# hexg-001.net
KiCad netlist of a schematic drawn in EAGLE
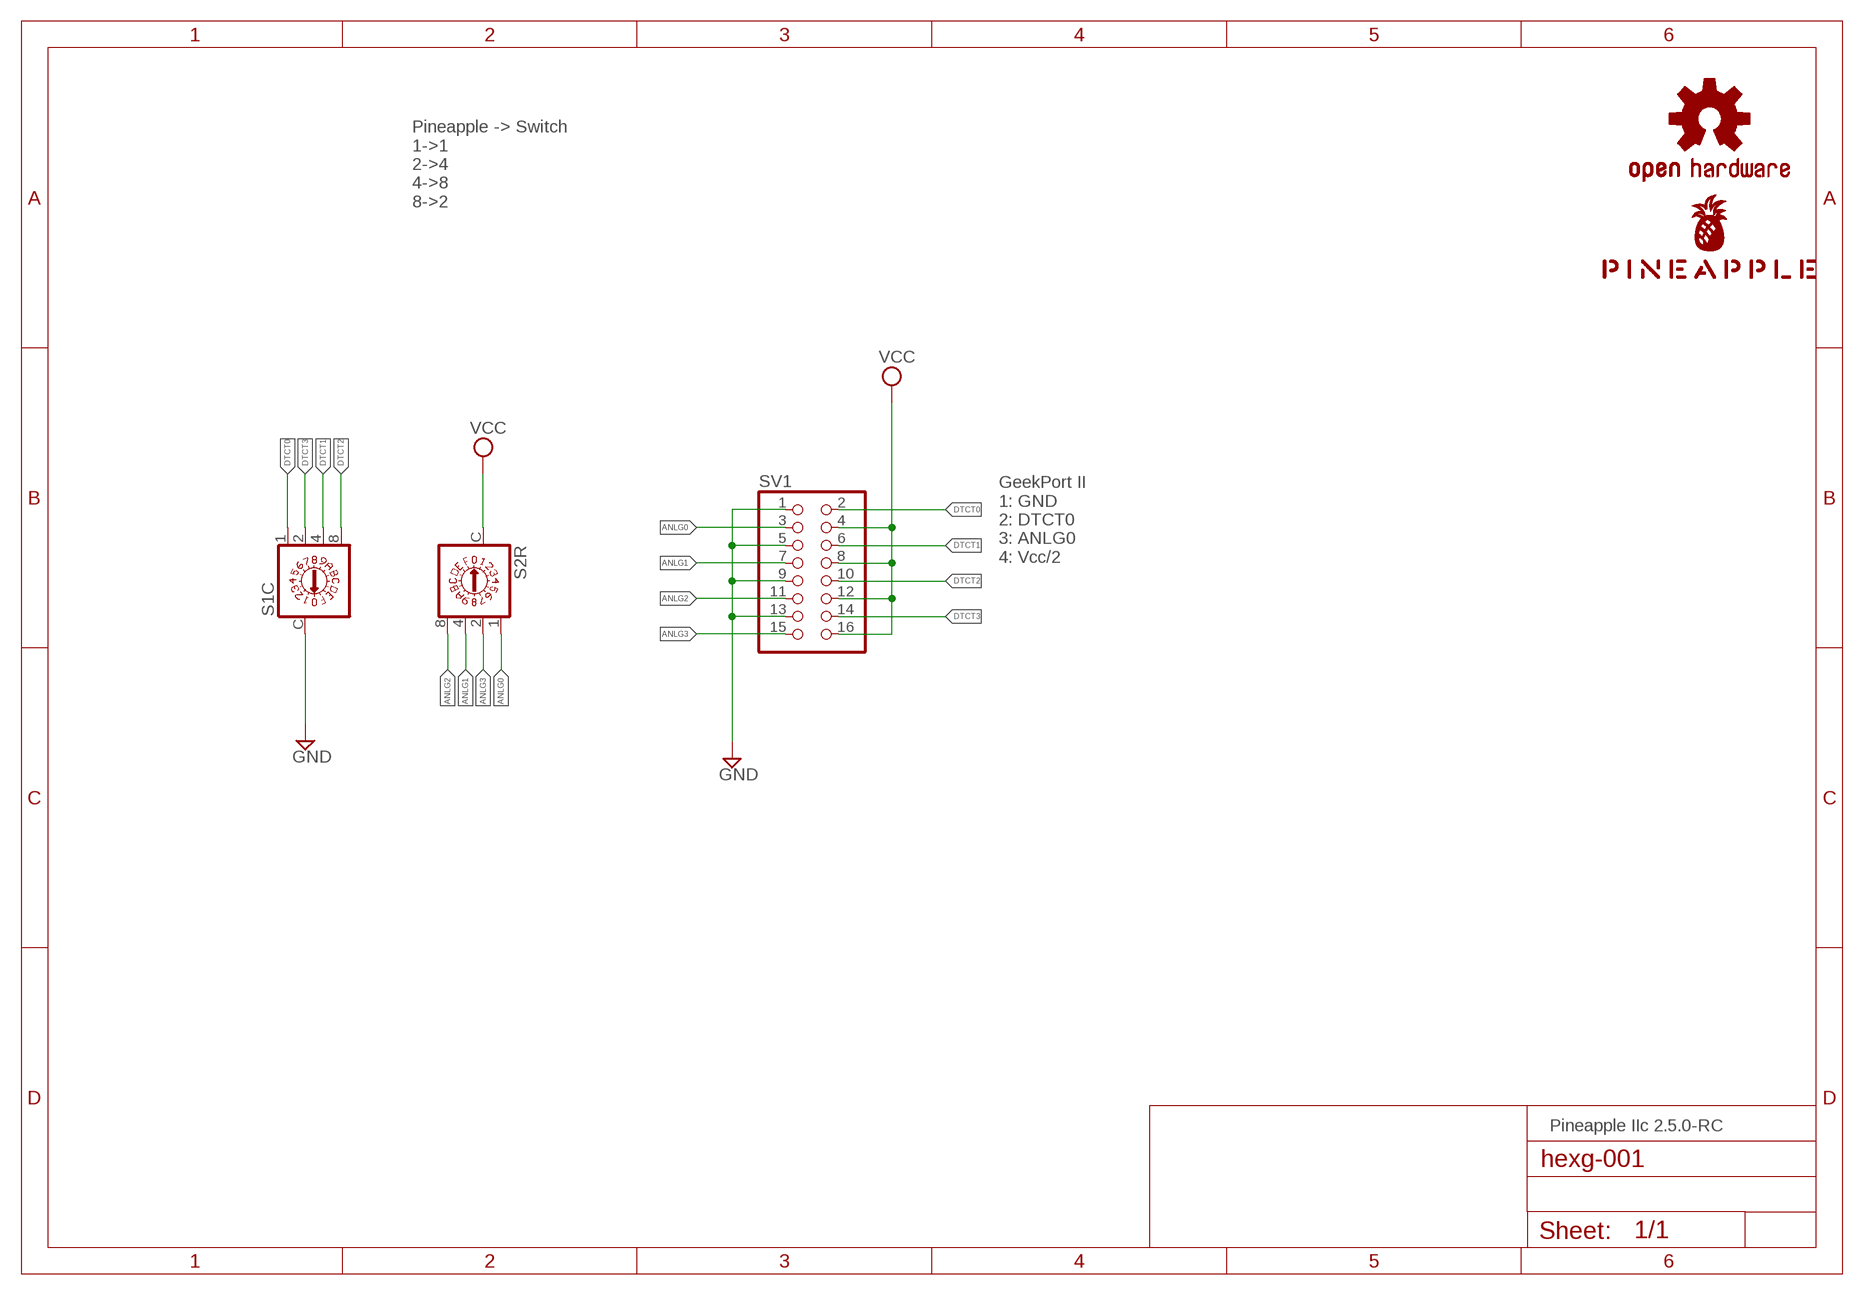
[diagram p0: schematic, sheet 1]

(export (version "E")
  (design (tool "Eeschema 10.0.6"))
  (components
    (comp (ref "LOGO1")
      (value "OSHW-LOGOS-COPPER")
      (footprint "eagle-import:OSHW-LOGO-S_COPPER")
      (libsource (lib "eagle-import") (part "OSHW-LOGOS-COPPER"))
    )
    (comp (ref "S1C")
      (value "A1353HEX")
      (footprint "eagle-import:A1353HEX")
      (libsource (lib "eagle-import") (part "A1353HEX"))
    )
    (comp (ref "S2R")
      (value "A1353HEX")
      (footprint "eagle-import:A1353HEX")
      (libsource (lib "eagle-import") (part "A1353HEX"))
    )
    (comp (ref "SV1")
      (value "PINHD-2X8")
      (footprint "eagle-import:2X08")
      (libsource (lib "eagle-import") (part "PINHD-2X8"))
    )
    (comp (ref "U$1")
      (value "PINEAPPLE450_SILK")
      (footprint "eagle-import:PINEAPPLE450_SILK")
      (libsource (lib "eagle-import") (part "PINEAPPLE450_SILK"))
    )
  )
  (nets
    (net (code "1") (name "ANLG0") (class "Default")
      (node (ref "S2R") (pin "1") (pinfunction "1_1") (pintype "passive"))
      (node (ref "SV1") (pin "3") (pinfunction "3_3") (pintype "passive"))
    )
    (net (code "2") (name "ANLG1") (class "Default")
      (node (ref "S2R") (pin "4") (pinfunction "4_4") (pintype "passive"))
      (node (ref "SV1") (pin "7") (pinfunction "7_7") (pintype "passive"))
    )
    (net (code "3") (name "ANLG2") (class "Default")
      (node (ref "S2R") (pin "8") (pinfunction "8_8") (pintype "passive"))
      (node (ref "SV1") (pin "11") (pinfunction "11_11") (pintype "passive"))
    )
    (net (code "4") (name "ANLG3") (class "Default")
      (node (ref "S2R") (pin "2") (pinfunction "2_2") (pintype "passive"))
      (node (ref "SV1") (pin "15") (pinfunction "15_15") (pintype "passive"))
    )
    (net (code "5") (name "DTCT0") (class "Default")
      (node (ref "S1C") (pin "1") (pinfunction "1_1") (pintype "passive"))
      (node (ref "SV1") (pin "2") (pinfunction "2_2") (pintype "passive"))
    )
    (net (code "6") (name "DTCT1") (class "Default")
      (node (ref "S1C") (pin "4") (pinfunction "4_4") (pintype "passive"))
      (node (ref "SV1") (pin "6") (pinfunction "6_6") (pintype "passive"))
    )
    (net (code "7") (name "DTCT2") (class "Default")
      (node (ref "S1C") (pin "8") (pinfunction "8_8") (pintype "passive"))
      (node (ref "SV1") (pin "10") (pinfunction "10_10") (pintype "passive"))
    )
    (net (code "8") (name "DTCT3") (class "Default")
      (node (ref "S1C") (pin "2") (pinfunction "2_2") (pintype "passive"))
      (node (ref "SV1") (pin "14") (pinfunction "14_14") (pintype "passive"))
    )
    (net (code "9") (name "GND") (class "Default")
      (node (ref "S1C") (pin "C") (pinfunction "C_C") (pintype "passive"))
      (node (ref "SV1") (pin "1") (pinfunction "1_1") (pintype "passive"))
      (node (ref "SV1") (pin "13") (pinfunction "13_13") (pintype "passive"))
      (node (ref "SV1") (pin "5") (pinfunction "5_5") (pintype "passive"))
      (node (ref "SV1") (pin "9") (pinfunction "9_9") (pintype "passive"))
    )
    (net (code "10") (name "VCC") (class "Default")
      (node (ref "S2R") (pin "C") (pinfunction "C_C") (pintype "passive"))
      (node (ref "SV1") (pin "12") (pinfunction "12_12") (pintype "passive"))
      (node (ref "SV1") (pin "16") (pinfunction "16_16") (pintype "passive"))
      (node (ref "SV1") (pin "4") (pinfunction "4_4") (pintype "passive"))
      (node (ref "SV1") (pin "8") (pinfunction "8_8") (pintype "passive"))
    )
  )
)
